# blink1mk3_005t6_4L.net
KiCad netlist of a schematic drawn in EAGLE
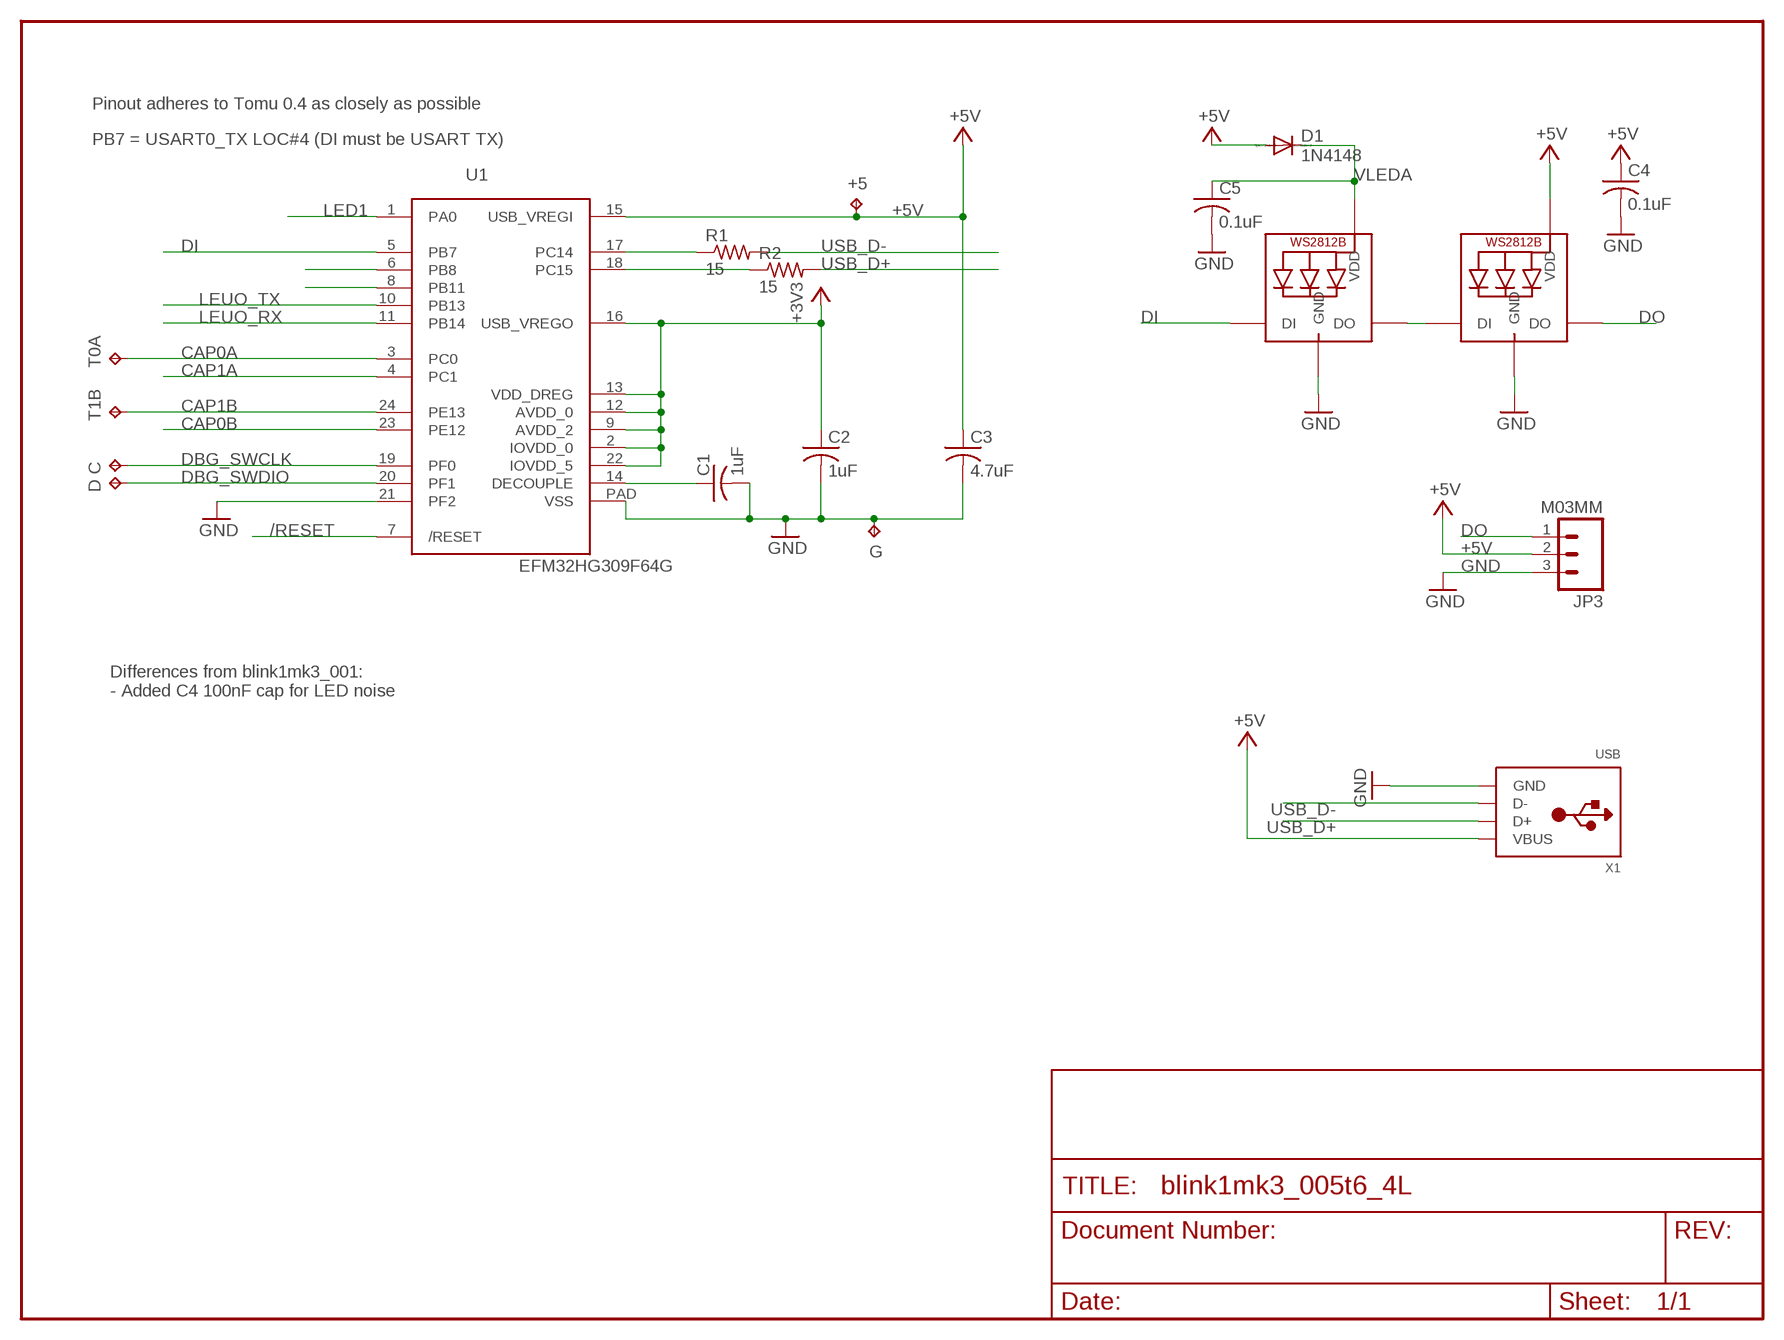
[diagram p0: schematic, sheet 1]

(export (version "E")
  (design (tool "Eeschema 10.0.6"))
  (components
    (comp (ref "+5")
      (value "TPTP10R")
      (footprint "eagle-import:TP10R")
      (libsource (lib "eagle-import") (part "TPTP10R"))
    )
    (comp (ref "C")
      (value "TPTP10R")
      (footprint "eagle-import:TP10R")
      (libsource (lib "eagle-import") (part "TPTP10R"))
    )
    (comp (ref "C1")
      (value "1uF")
      (footprint "eagle-import:C0402")
      (libsource (lib "eagle-import") (part "C-USC0402"))
    )
    (comp (ref "C2")
      (value "1uF")
      (footprint "eagle-import:C0402")
      (libsource (lib "eagle-import") (part "C-USC0402"))
    )
    (comp (ref "C3")
      (value "4.7uF")
      (footprint "eagle-import:C0402")
      (libsource (lib "eagle-import") (part "C-USC0402"))
    )
    (comp (ref "C4")
      (value "0.1uF")
      (footprint "eagle-import:C0402")
      (libsource (lib "eagle-import") (part "C-USC0402"))
    )
    (comp (ref "C5")
      (value "0.1uF")
      (footprint "eagle-import:C0402")
      (libsource (lib "eagle-import") (part "C-USC0402"))
    )
    (comp (ref "D")
      (value "TPTP10R")
      (footprint "eagle-import:TP10R")
      (libsource (lib "eagle-import") (part "TPTP10R"))
    )
    (comp (ref "D1")
      (value "1N4148")
      (footprint "eagle-import:SOD523")
      (libsource (lib "eagle-import") (part "DIODE-SOD523"))
    )
    (comp (ref "G")
      (value "TPTP10R")
      (footprint "eagle-import:TP10R")
      (libsource (lib "eagle-import") (part "TPTP10R"))
    )
    (comp (ref "JP3")
      (value "M03MM")
      (footprint "eagle-import:1X03-1.5MM")
      (libsource (lib "eagle-import") (part "M03MM"))
    )
    (comp (ref "LED1")
      (value "SK6812")
      (footprint "eagle-import:WS2812B")
      (libsource (lib "eagle-import") (part "WS2812B5050"))
    )
    (comp (ref "LED2")
      (value "SK6812")
      (footprint "eagle-import:WS2812B")
      (libsource (lib "eagle-import") (part "WS2812B5050"))
    )
    (comp (ref "R1")
      (value "15")
      (footprint "eagle-import:R0402")
      (libsource (lib "eagle-import") (part "R-US_R0402"))
    )
    (comp (ref "R2")
      (value "15")
      (footprint "eagle-import:R0402")
      (libsource (lib "eagle-import") (part "R-US_R0402"))
    )
    (comp (ref "T0A")
      (value "TPTP15R")
      (footprint "eagle-import:TP15R")
      (libsource (lib "eagle-import") (part "TPTP15R"))
    )
    (comp (ref "T1B")
      (value "TPTP15R")
      (footprint "eagle-import:TP15R")
      (libsource (lib "eagle-import") (part "TPTP15R"))
    )
    (comp (ref "U1")
      (value "EFM32HG309F64G")
      (footprint "eagle-import:QFN24PAD")
      (libsource (lib "eagle-import") (part "EFM32HG309F64G"))
    )
    (comp (ref "X1")
      (value "USB")
      (footprint "eagle-import:MOLEX-48037-1000")
      (libsource (lib "eagle-import") (part "USB"))
    )
  )
  (nets
    (net (code "1") (name "+3V3") (class "Default")
      (node (ref "C2") (pin "1") (pinfunction "1_1") (pintype "passive"))
      (node (ref "U1") (pin "12") (pinfunction "AVDD_0_12") (pintype "bidirectional"))
      (node (ref "U1") (pin "13") (pinfunction "VDD_DREG_13") (pintype "bidirectional"))
      (node (ref "U1") (pin "16") (pinfunction "USB_VREGO_16") (pintype "bidirectional"))
      (node (ref "U1") (pin "2") (pinfunction "IOVDD_0_2") (pintype "bidirectional"))
      (node (ref "U1") (pin "22") (pinfunction "IOVDD_5_22") (pintype "bidirectional"))
      (node (ref "U1") (pin "9") (pinfunction "AVDD_2_9") (pintype "bidirectional"))
    )
    (net (code "2") (name "+5V") (class "Default")
      (node (ref "+5") (pin "TP") (pinfunction "TP_TP") (pintype "input"))
      (node (ref "C3") (pin "1") (pinfunction "1_1") (pintype "passive"))
      (node (ref "C4") (pin "1") (pinfunction "1_1") (pintype "passive"))
      (node (ref "D1") (pin "A") (pinfunction "A_A") (pintype "passive"))
      (node (ref "JP3") (pin "2") (pinfunction "2_2") (pintype "passive"))
      (node (ref "LED2") (pin "1-VDD") (pinfunction "VDD_1-VDD") (pintype "power_in"))
      (node (ref "U1") (pin "15") (pinfunction "USB_VREGI_15") (pintype "bidirectional"))
      (node (ref "X1") (pin "1") (pinfunction "VBUS_1") (pintype "power_in"))
    )
    (net (code "3") (name "/CAP0A") (class "Default")
      (node (ref "T0A") (pin "TP") (pinfunction "TP_TP") (pintype "input"))
      (node (ref "U1") (pin "3") (pinfunction "PC0_3") (pintype "bidirectional"))
    )
    (net (code "4") (name "/CAP0B") (class "Default")
      (node (ref "U1") (pin "23") (pinfunction "PE12_23") (pintype "bidirectional"))
    )
    (net (code "5") (name "/CAP1A") (class "Default")
      (node (ref "U1") (pin "4") (pinfunction "PC1_4") (pintype "bidirectional"))
    )
    (net (code "6") (name "/CAP1B") (class "Default")
      (node (ref "T1B") (pin "TP") (pinfunction "TP_TP") (pintype "input"))
      (node (ref "U1") (pin "24") (pinfunction "PE13_24") (pintype "bidirectional"))
    )
    (net (code "7") (name "/DBG_SWCLK") (class "Default")
      (node (ref "C") (pin "TP") (pinfunction "TP_TP") (pintype "input"))
      (node (ref "U1") (pin "19") (pinfunction "PF0_19") (pintype "bidirectional"))
    )
    (net (code "8") (name "/DBG_SWDIO") (class "Default")
      (node (ref "D") (pin "TP") (pinfunction "TP_TP") (pintype "input"))
      (node (ref "U1") (pin "20") (pinfunction "PF1_20") (pintype "bidirectional"))
    )
    (net (code "9") (name "/DI") (class "Default")
      (node (ref "LED1") (pin "4-DIN") (pinfunction "DI_4-DIN") (pintype "input"))
      (node (ref "U1") (pin "5") (pinfunction "PB7_5") (pintype "bidirectional"))
    )
    (net (code "10") (name "/DO") (class "Default")
      (node (ref "JP3") (pin "1") (pinfunction "1_1") (pintype "passive"))
      (node (ref "LED2") (pin "2-DOUT") (pinfunction "DO_2-DOUT") (pintype "output"))
    )
    (net (code "11") (name "/LED1") (class "Default")
      (node (ref "U1") (pin "1") (pinfunction "PA0_1") (pintype "bidirectional"))
    )
    (net (code "12") (name "/LEUO_RX") (class "Default")
      (node (ref "U1") (pin "11") (pinfunction "PB14_11") (pintype "bidirectional"))
    )
    (net (code "13") (name "/LEUO_TX") (class "Default")
      (node (ref "U1") (pin "10") (pinfunction "PB13_10") (pintype "bidirectional"))
    )
    (net (code "14") (name "/USB_D+") (class "Default")
      (node (ref "R2") (pin "2") (pinfunction "2_2") (pintype "passive"))
      (node (ref "X1") (pin "3") (pinfunction "D+_3") (pintype "bidirectional"))
    )
    (net (code "15") (name "/USB_D-") (class "Default")
      (node (ref "R1") (pin "2") (pinfunction "2_2") (pintype "passive"))
      (node (ref "X1") (pin "2") (pinfunction "D-_2") (pintype "bidirectional"))
    )
    (net (code "16") (name "/VLEDA") (class "Default")
      (node (ref "C5") (pin "1") (pinfunction "1_1") (pintype "passive"))
      (node (ref "D1") (pin "C") (pinfunction "C_C") (pintype "passive"))
      (node (ref "LED1") (pin "1-VDD") (pinfunction "VDD_1-VDD") (pintype "power_in"))
    )
    (net (code "17") (name "/{slash}RESET") (class "Default")
      (node (ref "U1") (pin "7") (pinfunction "/RESET_7") (pintype "bidirectional"))
    )
    (net (code "18") (name "GND") (class "Default")
      (node (ref "C1") (pin "2") (pinfunction "2_2") (pintype "passive"))
      (node (ref "C2") (pin "2") (pinfunction "2_2") (pintype "passive"))
      (node (ref "C3") (pin "2") (pinfunction "2_2") (pintype "passive"))
      (node (ref "C4") (pin "2") (pinfunction "2_2") (pintype "passive"))
      (node (ref "C5") (pin "2") (pinfunction "2_2") (pintype "passive"))
      (node (ref "G") (pin "TP") (pinfunction "TP_TP") (pintype "input"))
      (node (ref "JP3") (pin "3") (pinfunction "3_3") (pintype "passive"))
      (node (ref "LED1") (pin "3-GND") (pinfunction "GND_3-GND") (pintype "power_in"))
      (node (ref "LED2") (pin "3-GND") (pinfunction "GND_3-GND") (pintype "power_in"))
      (node (ref "U1") (pin "21") (pinfunction "PF2_21") (pintype "bidirectional"))
      (node (ref "U1") (pin "PAD") (pinfunction "VSS_PAD") (pintype "bidirectional"))
      (node (ref "X1") (pin "4") (pinfunction "GND_4") (pintype "power_in"))
    )
    (net (code "19") (name "Net-(LED1-DO)") (class "Default")
      (node (ref "LED1") (pin "2-DOUT") (pinfunction "DO_2-DOUT") (pintype "output"))
      (node (ref "LED2") (pin "4-DIN") (pinfunction "DI_4-DIN") (pintype "input"))
    )
    (net (code "20") (name "Net-(U1-DECOUPLE)") (class "Default")
      (node (ref "C1") (pin "1") (pinfunction "1_1") (pintype "passive"))
      (node (ref "U1") (pin "14") (pinfunction "DECOUPLE_14") (pintype "bidirectional"))
    )
    (net (code "21") (name "Net-(U1-PC14)") (class "Default")
      (node (ref "R1") (pin "1") (pinfunction "1_1") (pintype "passive"))
      (node (ref "U1") (pin "17") (pinfunction "PC14_17") (pintype "bidirectional"))
    )
    (net (code "22") (name "Net-(U1-PC15)") (class "Default")
      (node (ref "R2") (pin "1") (pinfunction "1_1") (pintype "passive"))
      (node (ref "U1") (pin "18") (pinfunction "PC15_18") (pintype "bidirectional"))
    )
    (net (code "23") (name "unconnected-(U1-PB8-Pad6)") (class "Default")
      (node (ref "U1") (pin "6") (pinfunction "PB8_6") (pintype "bidirectional"))
    )
    (net (code "24") (name "unconnected-(U1-PB11-Pad8)") (class "Default")
      (node (ref "U1") (pin "8") (pinfunction "PB11_8") (pintype "bidirectional"))
    )
  )
)
